# MRCS-ODX-8.net
KiCad netlist of a schematic drawn in EAGLE
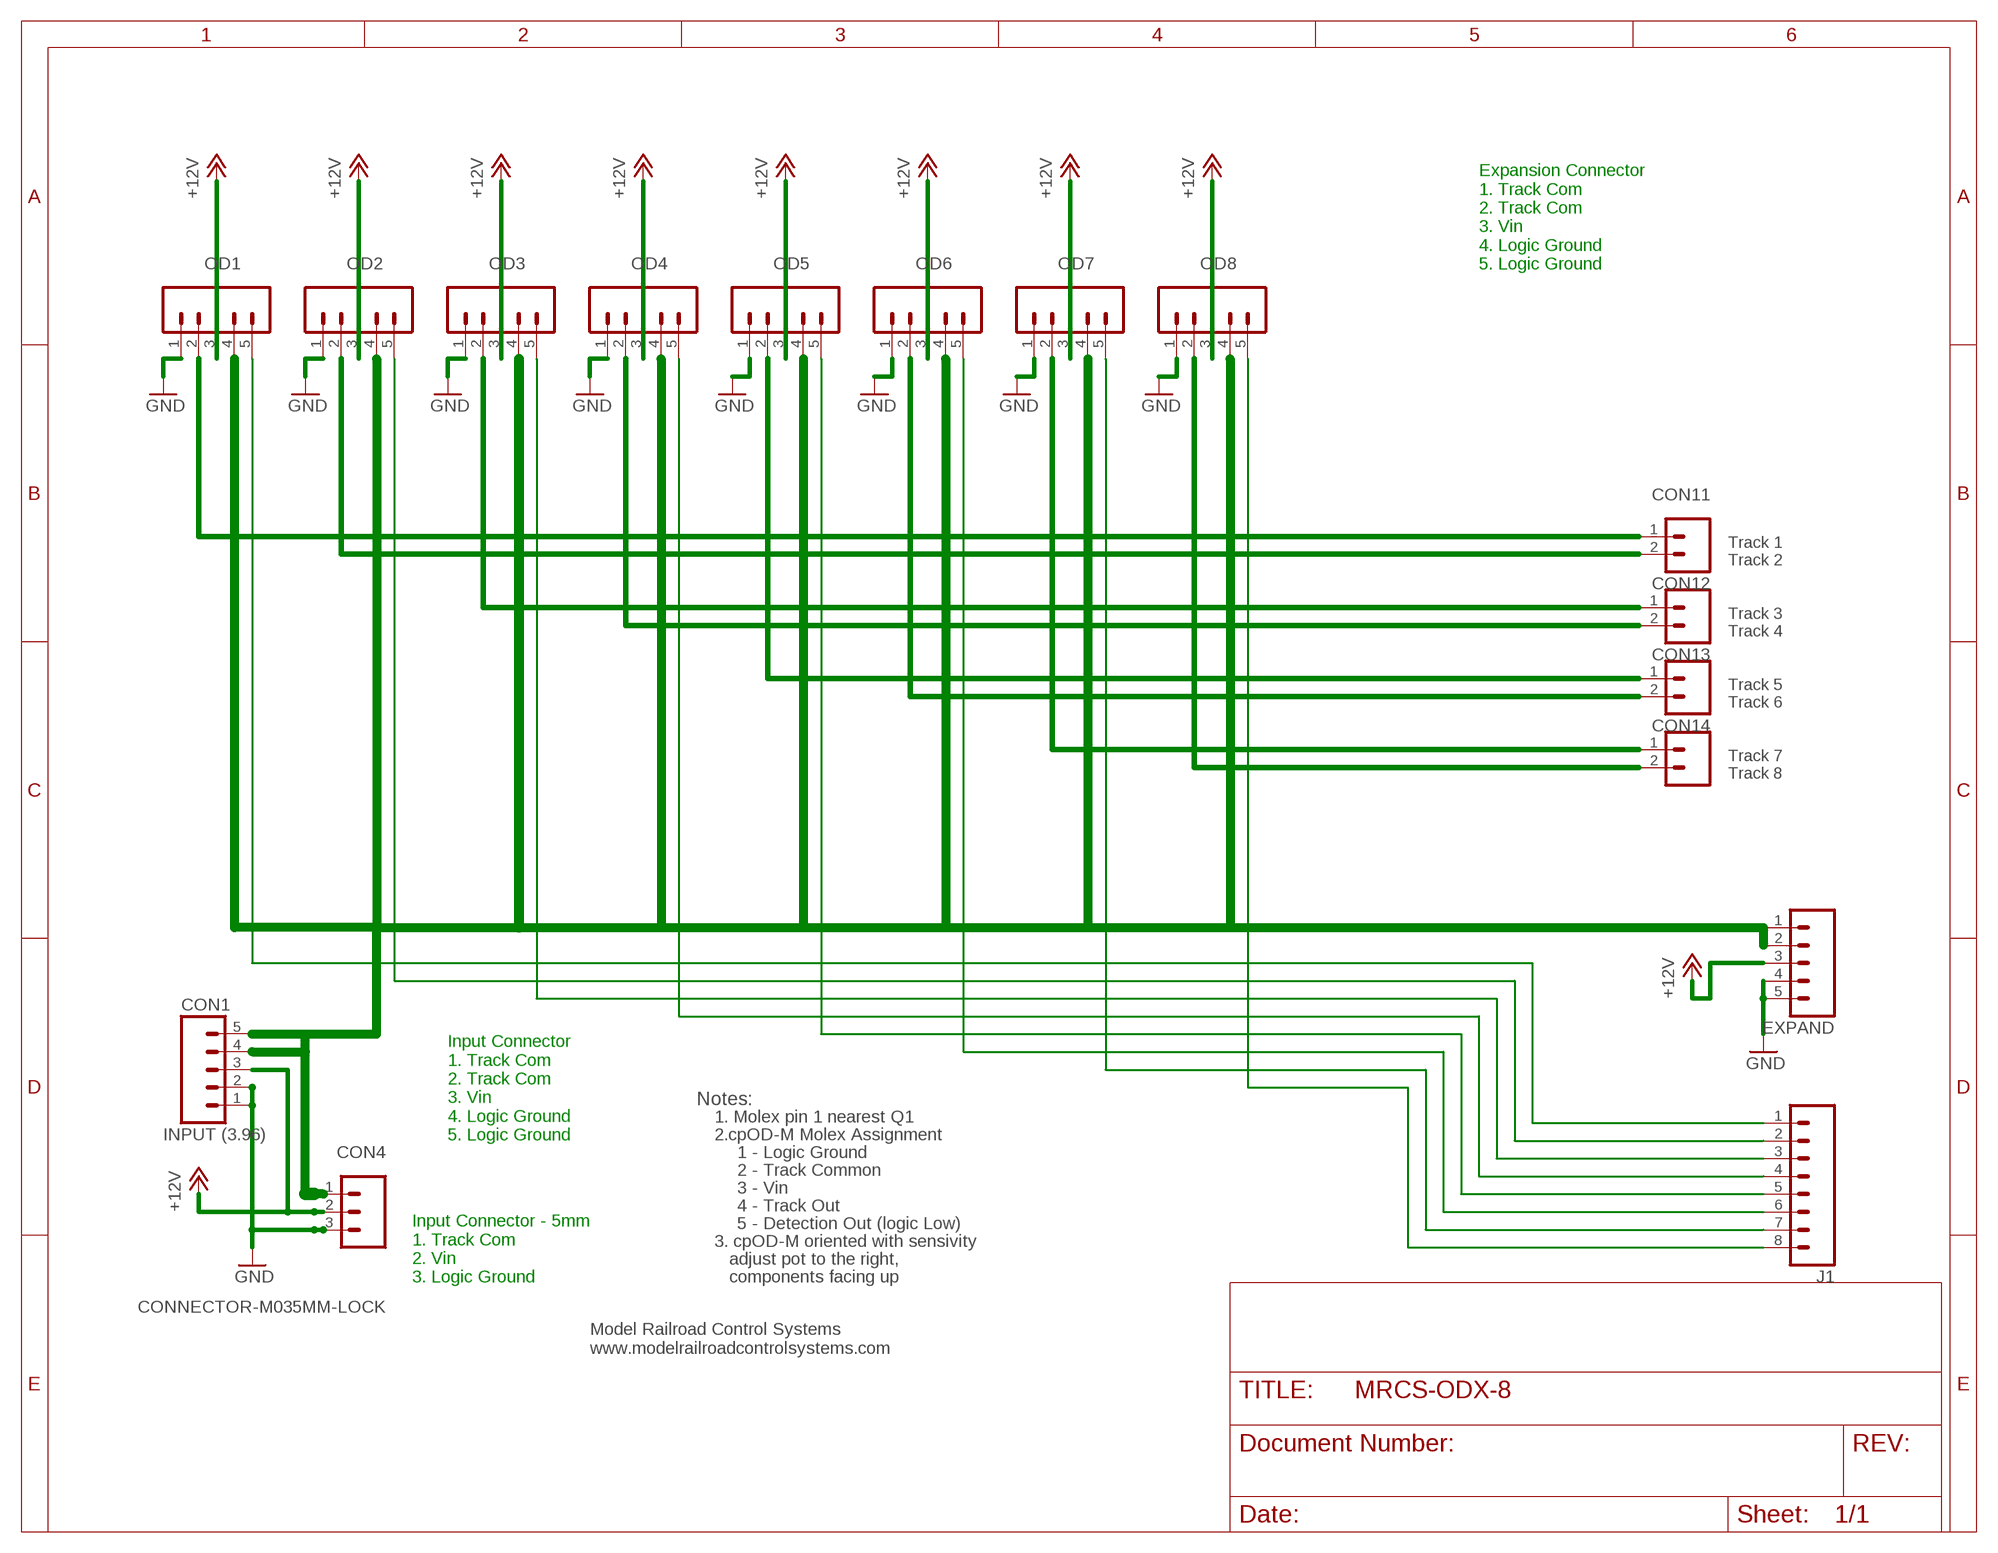
[diagram p0: schematic, sheet 1]

(export (version "E")
  (design (tool "Eeschema 10.0.6"))
  (components
    (comp (ref "CON1")
      (value "INPUT (3.96)")
      (footprint "eagle-import:KK-156-5")
      (libsource (lib "eagle-import") (part "CONNECTOR-M051.56"))
    )
    (comp (ref "CON4")
      (value "CONNECTOR-M035MM-LOCK")
      (footprint "eagle-import:SCREWTERMINAL-5MM-3")
      (libsource (lib "eagle-import") (part "CONNECTOR-M035MM-LOCK"))
    )
    (comp (ref "CON11")
      (value "CONNECTOR-M025MM-LOCK")
      (footprint "eagle-import:SCREWTERMINAL-5MM-2")
      (libsource (lib "eagle-import") (part "CONNECTOR-M025MM-LOCK"))
    )
    (comp (ref "CON12")
      (value "CONNECTOR-M025MM-LOCK")
      (footprint "eagle-import:SCREWTERMINAL-5MM-2")
      (libsource (lib "eagle-import") (part "CONNECTOR-M025MM-LOCK"))
    )
    (comp (ref "CON13")
      (value "CONNECTOR-M025MM-LOCK")
      (footprint "eagle-import:SCREWTERMINAL-5MM-2")
      (libsource (lib "eagle-import") (part "CONNECTOR-M025MM-LOCK"))
    )
    (comp (ref "CON14")
      (value "CONNECTOR-M025MM-LOCK")
      (footprint "eagle-import:SCREWTERMINAL-5MM-2")
      (libsource (lib "eagle-import") (part "CONNECTOR-M025MM-LOCK"))
    )
    (comp (ref "EXPAND")
      (value "CONNECTOR-M051.56")
      (footprint "eagle-import:KK-156-5")
      (libsource (lib "eagle-import") (part "CONNECTOR-M051.56"))
    )
    (comp (ref "J1")
      (value "CONNECTOR-M08LOCK")
      (footprint "eagle-import:1X08_LOCK")
      (libsource (lib "eagle-import") (part "CONNECTOR-M08LOCK"))
    )
    (comp (ref "OD1")
      (value "CONNECTOR-M051.56")
      (footprint "eagle-import:KK-156-5")
      (libsource (lib "eagle-import") (part "CONNECTOR-M051.56"))
    )
    (comp (ref "OD2")
      (value "CONNECTOR-M051.56")
      (footprint "eagle-import:KK-156-5")
      (libsource (lib "eagle-import") (part "CONNECTOR-M051.56"))
    )
    (comp (ref "OD3")
      (value "CONNECTOR-M051.56")
      (footprint "eagle-import:KK-156-5")
      (libsource (lib "eagle-import") (part "CONNECTOR-M051.56"))
    )
    (comp (ref "OD4")
      (value "CONNECTOR-M051.56")
      (footprint "eagle-import:KK-156-5")
      (libsource (lib "eagle-import") (part "CONNECTOR-M051.56"))
    )
    (comp (ref "OD5")
      (value "CONNECTOR-M051.56")
      (footprint "eagle-import:KK-156-5")
      (libsource (lib "eagle-import") (part "CONNECTOR-M051.56"))
    )
    (comp (ref "OD6")
      (value "CONNECTOR-M051.56")
      (footprint "eagle-import:KK-156-5")
      (libsource (lib "eagle-import") (part "CONNECTOR-M051.56"))
    )
    (comp (ref "OD7")
      (value "CONNECTOR-M051.56")
      (footprint "eagle-import:KK-156-5")
      (libsource (lib "eagle-import") (part "CONNECTOR-M051.56"))
    )
    (comp (ref "OD8")
      (value "CONNECTOR-M051.56")
      (footprint "eagle-import:KK-156-5")
      (libsource (lib "eagle-import") (part "CONNECTOR-M051.56"))
    )
  )
  (nets
    (net (code "1") (name "+12V") (class "Default")
      (node (ref "CON1") (pin "3") (pinfunction "3_3") (pintype "passive"))
      (node (ref "CON4") (pin "2") (pinfunction "2_2") (pintype "passive"))
      (node (ref "EXPAND") (pin "3") (pinfunction "3_3") (pintype "passive"))
      (node (ref "OD1") (pin "3") (pinfunction "3_3") (pintype "passive"))
      (node (ref "OD2") (pin "3") (pinfunction "3_3") (pintype "passive"))
      (node (ref "OD3") (pin "3") (pinfunction "3_3") (pintype "passive"))
      (node (ref "OD4") (pin "3") (pinfunction "3_3") (pintype "passive"))
      (node (ref "OD5") (pin "3") (pinfunction "3_3") (pintype "passive"))
      (node (ref "OD6") (pin "3") (pinfunction "3_3") (pintype "passive"))
      (node (ref "OD7") (pin "3") (pinfunction "3_3") (pintype "passive"))
      (node (ref "OD8") (pin "3") (pinfunction "3_3") (pintype "passive"))
    )
    (net (code "2") (name "GND") (class "Default")
      (node (ref "CON1") (pin "1") (pinfunction "1_1") (pintype "passive"))
      (node (ref "CON1") (pin "2") (pinfunction "2_2") (pintype "passive"))
      (node (ref "CON4") (pin "3") (pinfunction "3_3") (pintype "passive"))
      (node (ref "EXPAND") (pin "4") (pinfunction "4_4") (pintype "passive"))
      (node (ref "EXPAND") (pin "5") (pinfunction "5_5") (pintype "passive"))
      (node (ref "OD1") (pin "1") (pinfunction "1_1") (pintype "passive"))
      (node (ref "OD2") (pin "1") (pinfunction "1_1") (pintype "passive"))
      (node (ref "OD3") (pin "1") (pinfunction "1_1") (pintype "passive"))
      (node (ref "OD4") (pin "1") (pinfunction "1_1") (pintype "passive"))
      (node (ref "OD5") (pin "1") (pinfunction "1_1") (pintype "passive"))
      (node (ref "OD6") (pin "1") (pinfunction "1_1") (pintype "passive"))
      (node (ref "OD7") (pin "1") (pinfunction "1_1") (pintype "passive"))
      (node (ref "OD8") (pin "1") (pinfunction "1_1") (pintype "passive"))
    )
    (net (code "3") (name "Net-(CON1-Pad4)") (class "Default")
      (node (ref "CON1") (pin "4") (pinfunction "4_4") (pintype "passive"))
      (node (ref "CON1") (pin "5") (pinfunction "5_5") (pintype "passive"))
      (node (ref "CON4") (pin "1") (pinfunction "1_1") (pintype "passive"))
      (node (ref "EXPAND") (pin "1") (pinfunction "1_1") (pintype "passive"))
      (node (ref "EXPAND") (pin "2") (pinfunction "2_2") (pintype "passive"))
      (node (ref "OD1") (pin "4") (pinfunction "4_4") (pintype "passive"))
      (node (ref "OD2") (pin "4") (pinfunction "4_4") (pintype "passive"))
      (node (ref "OD3") (pin "4") (pinfunction "4_4") (pintype "passive"))
      (node (ref "OD4") (pin "4") (pinfunction "4_4") (pintype "passive"))
      (node (ref "OD5") (pin "4") (pinfunction "4_4") (pintype "passive"))
      (node (ref "OD6") (pin "4") (pinfunction "4_4") (pintype "passive"))
      (node (ref "OD7") (pin "4") (pinfunction "4_4") (pintype "passive"))
      (node (ref "OD8") (pin "4") (pinfunction "4_4") (pintype "passive"))
    )
    (net (code "4") (name "Net-(CON11-A)") (class "Default")
      (node (ref "CON11") (pin "1") (pinfunction "A_1") (pintype "passive"))
      (node (ref "OD1") (pin "2") (pinfunction "2_2") (pintype "passive"))
    )
    (net (code "5") (name "Net-(CON11-B)") (class "Default")
      (node (ref "CON11") (pin "2") (pinfunction "B_2") (pintype "passive"))
      (node (ref "OD2") (pin "2") (pinfunction "2_2") (pintype "passive"))
    )
    (net (code "6") (name "Net-(CON12-A)") (class "Default")
      (node (ref "CON12") (pin "1") (pinfunction "A_1") (pintype "passive"))
      (node (ref "OD3") (pin "2") (pinfunction "2_2") (pintype "passive"))
    )
    (net (code "7") (name "Net-(CON12-B)") (class "Default")
      (node (ref "CON12") (pin "2") (pinfunction "B_2") (pintype "passive"))
      (node (ref "OD4") (pin "2") (pinfunction "2_2") (pintype "passive"))
    )
    (net (code "8") (name "Net-(CON13-A)") (class "Default")
      (node (ref "CON13") (pin "1") (pinfunction "A_1") (pintype "passive"))
      (node (ref "OD5") (pin "2") (pinfunction "2_2") (pintype "passive"))
    )
    (net (code "9") (name "Net-(CON13-B)") (class "Default")
      (node (ref "CON13") (pin "2") (pinfunction "B_2") (pintype "passive"))
      (node (ref "OD6") (pin "2") (pinfunction "2_2") (pintype "passive"))
    )
    (net (code "10") (name "Net-(CON14-A)") (class "Default")
      (node (ref "CON14") (pin "1") (pinfunction "A_1") (pintype "passive"))
      (node (ref "OD7") (pin "2") (pinfunction "2_2") (pintype "passive"))
    )
    (net (code "11") (name "Net-(CON14-B)") (class "Default")
      (node (ref "CON14") (pin "2") (pinfunction "B_2") (pintype "passive"))
      (node (ref "OD8") (pin "2") (pinfunction "2_2") (pintype "passive"))
    )
    (net (code "12") (name "Net-(J1-Pad1)") (class "Default")
      (node (ref "J1") (pin "1") (pinfunction "1_1") (pintype "passive"))
      (node (ref "OD1") (pin "5") (pinfunction "5_5") (pintype "passive"))
    )
    (net (code "13") (name "Net-(J1-Pad2)") (class "Default")
      (node (ref "J1") (pin "2") (pinfunction "2_2") (pintype "passive"))
      (node (ref "OD2") (pin "5") (pinfunction "5_5") (pintype "passive"))
    )
    (net (code "14") (name "Net-(J1-Pad3)") (class "Default")
      (node (ref "J1") (pin "3") (pinfunction "3_3") (pintype "passive"))
      (node (ref "OD3") (pin "5") (pinfunction "5_5") (pintype "passive"))
    )
    (net (code "15") (name "Net-(J1-Pad4)") (class "Default")
      (node (ref "J1") (pin "4") (pinfunction "4_4") (pintype "passive"))
      (node (ref "OD4") (pin "5") (pinfunction "5_5") (pintype "passive"))
    )
    (net (code "16") (name "Net-(J1-Pad5)") (class "Default")
      (node (ref "J1") (pin "5") (pinfunction "5_5") (pintype "passive"))
      (node (ref "OD5") (pin "5") (pinfunction "5_5") (pintype "passive"))
    )
    (net (code "17") (name "Net-(J1-Pad6)") (class "Default")
      (node (ref "J1") (pin "6") (pinfunction "6_6") (pintype "passive"))
      (node (ref "OD6") (pin "5") (pinfunction "5_5") (pintype "passive"))
    )
    (net (code "18") (name "Net-(J1-Pad7)") (class "Default")
      (node (ref "J1") (pin "7") (pinfunction "7_7") (pintype "passive"))
      (node (ref "OD7") (pin "5") (pinfunction "5_5") (pintype "passive"))
    )
    (net (code "19") (name "Net-(J1-Pad8)") (class "Default")
      (node (ref "J1") (pin "8") (pinfunction "8_8") (pintype "passive"))
      (node (ref "OD8") (pin "5") (pinfunction "5_5") (pintype "passive"))
    )
  )
)
